# zhab-duino.net
KiCad netlist of a schematic drawn in EAGLE
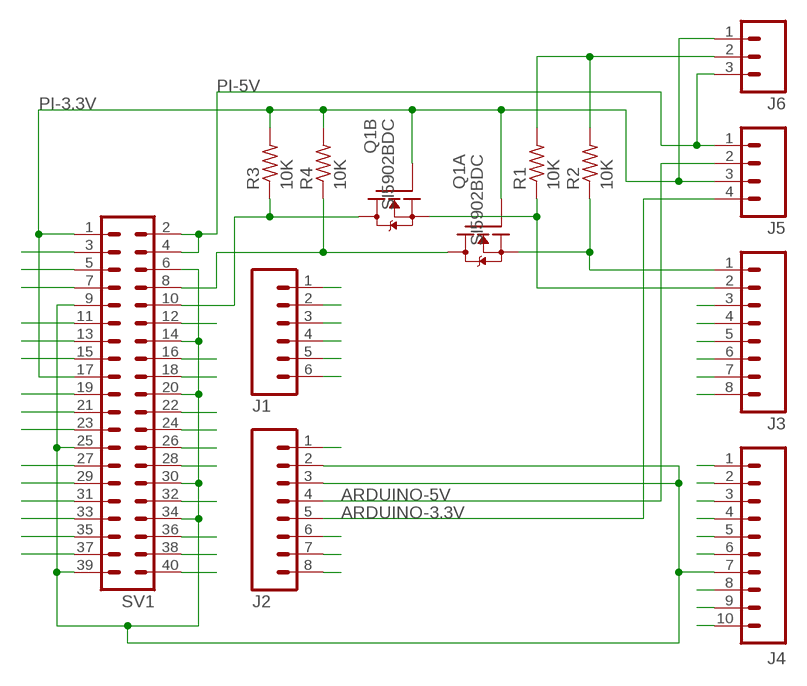
[diagram p0: schematic, sheet 1]

(export (version "E")
  (design (tool "Eeschema 10.0.6"))
  (components
    (comp (ref "J1")
      (value "M06NO_SILK_FEMALE_PTH")
      (footprint "eagle-import:1X06_NO_SILK")
      (libsource (lib "eagle-import") (part "M06NO_SILK_FEMALE_PTH"))
    )
    (comp (ref "J2")
      (value "M08NO_SILK_FEMALE_PTH")
      (footprint "eagle-import:1X08_NO_SILK")
      (libsource (lib "eagle-import") (part "M08NO_SILK_FEMALE_PTH"))
    )
    (comp (ref "J3")
      (value "M08NO_SILK_FEMALE_PTH")
      (footprint "eagle-import:1X08_NO_SILK")
      (libsource (lib "eagle-import") (part "M08NO_SILK_FEMALE_PTH"))
    )
    (comp (ref "J4")
      (value "M10NO_SILK_PTH_FEMALE")
      (footprint "eagle-import:1X10_NO_SILK")
      (libsource (lib "eagle-import") (part "M10NO_SILK_PTH_FEMALE"))
    )
    (comp (ref "J5")
      (value "M04NO_SILK_ALL_ROUND")
      (footprint "eagle-import:1X04_NO_SILK_ALL_ROUND")
      (libsource (lib "eagle-import") (part "M04NO_SILK_ALL_ROUND"))
    )
    (comp (ref "J6")
      (value "M031X03_NO_SILK")
      (footprint "eagle-import:1X03_NO_SILK")
      (libsource (lib "eagle-import") (part "M031X03_NO_SILK"))
    )
    (comp (ref "Q1")
      (value "SI5902BDC")
      (footprint "eagle-import:1206-8CHIP-FET")
      (libsource (lib "eagle-import") (part "SI5902DC"))
    )
    (comp (ref "R1")
      (value "10K")
      (footprint "eagle-import:M1206")
      (libsource (lib "eagle-import") (part "R-US_M1206"))
    )
    (comp (ref "R2")
      (value "10K")
      (footprint "eagle-import:M1206")
      (libsource (lib "eagle-import") (part "R-US_M1206"))
    )
    (comp (ref "R3")
      (value "10K")
      (footprint "eagle-import:M1206")
      (libsource (lib "eagle-import") (part "R-US_M1206"))
    )
    (comp (ref "R4")
      (value "10K")
      (footprint "eagle-import:M1206")
      (libsource (lib "eagle-import") (part "R-US_M1206"))
    )
    (comp (ref "SV1")
      (value "MA20-2")
      (footprint "eagle-import:MA20-2")
      (libsource (lib "eagle-import") (part "MA20-2"))
    )
  )
  (nets
    (net (code "1") (name "/ARDUINO-3.3V") (class "Default")
      (node (ref "J2") (pin "5") (pinfunction "5_5") (pintype "passive"))
      (node (ref "J5") (pin "4") (pinfunction "4_4") (pintype "passive"))
    )
    (net (code "2") (name "/ARDUINO-5V") (class "Default")
      (node (ref "J2") (pin "4") (pinfunction "4_4") (pintype "passive"))
      (node (ref "J5") (pin "2") (pinfunction "2_2") (pintype "passive"))
    )
    (net (code "3") (name "/PI-3.3V") (class "Default")
      (node (ref "J5") (pin "3") (pinfunction "3_3") (pintype "passive"))
      (node (ref "J6") (pin "1") (pinfunction "1_1") (pintype "passive"))
      (node (ref "Q1") (pin "2") (pinfunction "G_2") (pintype "passive"))
      (node (ref "Q1") (pin "4") (pinfunction "G_4") (pintype "passive"))
      (node (ref "R3") (pin "2") (pinfunction "2_2") (pintype "passive"))
      (node (ref "R4") (pin "2") (pinfunction "2_2") (pintype "passive"))
      (node (ref "SV1") (pin "1") (pinfunction "1_1") (pintype "passive"))
      (node (ref "SV1") (pin "17") (pinfunction "17_17") (pintype "passive"))
    )
    (net (code "4") (name "/PI-5V") (class "Default")
      (node (ref "J5") (pin "1") (pinfunction "1_1") (pintype "passive"))
      (node (ref "J6") (pin "3") (pinfunction "3_3") (pintype "passive"))
      (node (ref "SV1") (pin "2") (pinfunction "2_2") (pintype "passive"))
      (node (ref "SV1") (pin "4") (pinfunction "4_4") (pintype "passive"))
    )
    (net (code "5") (name "Net-(J2-Pad2)") (class "Default")
      (node (ref "J2") (pin "2") (pinfunction "2_2") (pintype "passive"))
      (node (ref "J2") (pin "3") (pinfunction "3_3") (pintype "passive"))
      (node (ref "J4") (pin "7") (pinfunction "7_7") (pintype "passive"))
      (node (ref "SV1") (pin "14") (pinfunction "14_14") (pintype "passive"))
      (node (ref "SV1") (pin "20") (pinfunction "20_20") (pintype "passive"))
      (node (ref "SV1") (pin "25") (pinfunction "25_25") (pintype "passive"))
      (node (ref "SV1") (pin "30") (pinfunction "30_30") (pintype "passive"))
      (node (ref "SV1") (pin "34") (pinfunction "34_34") (pintype "passive"))
      (node (ref "SV1") (pin "39") (pinfunction "39_39") (pintype "passive"))
      (node (ref "SV1") (pin "6") (pinfunction "6_6") (pintype "passive"))
      (node (ref "SV1") (pin "9") (pinfunction "9_9") (pintype "passive"))
    )
    (net (code "6") (name "Net-(J6-Pad2)") (class "Default")
      (node (ref "J6") (pin "2") (pinfunction "2_2") (pintype "passive"))
      (node (ref "R1") (pin "2") (pinfunction "2_2") (pintype "passive"))
      (node (ref "R2") (pin "2") (pinfunction "2_2") (pintype "passive"))
    )
    (net (code "7") (name "Net-(Q1A-D-Pad7)") (class "Default")
      (node (ref "Q1") (pin "7") (pinfunction "D_7") (pintype "passive"))
      (node (ref "Q1") (pin "8") (pinfunction "D_8") (pintype "passive"))
      (node (ref "R4") (pin "1") (pinfunction "1_1") (pintype "passive"))
      (node (ref "SV1") (pin "8") (pinfunction "8_8") (pintype "passive"))
    )
    (net (code "8") (name "Net-(Q1A-S)") (class "Default")
      (node (ref "J3") (pin "1") (pinfunction "1_1") (pintype "passive"))
      (node (ref "Q1") (pin "1") (pinfunction "S_1") (pintype "passive"))
      (node (ref "R2") (pin "1") (pinfunction "1_1") (pintype "passive"))
    )
    (net (code "9") (name "Net-(Q1B-D-Pad5)") (class "Default")
      (node (ref "Q1") (pin "5") (pinfunction "D_5") (pintype "passive"))
      (node (ref "Q1") (pin "6") (pinfunction "D_6") (pintype "passive"))
      (node (ref "R3") (pin "1") (pinfunction "1_1") (pintype "passive"))
      (node (ref "SV1") (pin "10") (pinfunction "10_10") (pintype "passive"))
    )
    (net (code "10") (name "Net-(Q1B-S)") (class "Default")
      (node (ref "J3") (pin "2") (pinfunction "2_2") (pintype "passive"))
      (node (ref "Q1") (pin "3") (pinfunction "S_3") (pintype "passive"))
      (node (ref "R1") (pin "1") (pinfunction "1_1") (pintype "passive"))
    )
    (net (code "11") (name "unconnected-(J1-Pad1)") (class "Default")
      (node (ref "J1") (pin "1") (pinfunction "1_1") (pintype "passive"))
    )
    (net (code "12") (name "unconnected-(J1-Pad2)") (class "Default")
      (node (ref "J1") (pin "2") (pinfunction "2_2") (pintype "passive"))
    )
    (net (code "13") (name "unconnected-(J1-Pad3)") (class "Default")
      (node (ref "J1") (pin "3") (pinfunction "3_3") (pintype "passive"))
    )
    (net (code "14") (name "unconnected-(J1-Pad4)") (class "Default")
      (node (ref "J1") (pin "4") (pinfunction "4_4") (pintype "passive"))
    )
    (net (code "15") (name "unconnected-(J1-Pad5)") (class "Default")
      (node (ref "J1") (pin "5") (pinfunction "5_5") (pintype "passive"))
    )
    (net (code "16") (name "unconnected-(J1-Pad6)") (class "Default")
      (node (ref "J1") (pin "6") (pinfunction "6_6") (pintype "passive"))
    )
    (net (code "17") (name "unconnected-(J2-Pad1)") (class "Default")
      (node (ref "J2") (pin "1") (pinfunction "1_1") (pintype "passive"))
    )
    (net (code "18") (name "unconnected-(J2-Pad6)") (class "Default")
      (node (ref "J2") (pin "6") (pinfunction "6_6") (pintype "passive"))
    )
    (net (code "19") (name "unconnected-(J2-Pad7)") (class "Default")
      (node (ref "J2") (pin "7") (pinfunction "7_7") (pintype "passive"))
    )
    (net (code "20") (name "unconnected-(J2-Pad8)") (class "Default")
      (node (ref "J2") (pin "8") (pinfunction "8_8") (pintype "passive"))
    )
    (net (code "21") (name "unconnected-(J3-Pad3)") (class "Default")
      (node (ref "J3") (pin "3") (pinfunction "3_3") (pintype "passive"))
    )
    (net (code "22") (name "unconnected-(J3-Pad4)") (class "Default")
      (node (ref "J3") (pin "4") (pinfunction "4_4") (pintype "passive"))
    )
    (net (code "23") (name "unconnected-(J3-Pad5)") (class "Default")
      (node (ref "J3") (pin "5") (pinfunction "5_5") (pintype "passive"))
    )
    (net (code "24") (name "unconnected-(J3-Pad6)") (class "Default")
      (node (ref "J3") (pin "6") (pinfunction "6_6") (pintype "passive"))
    )
    (net (code "25") (name "unconnected-(J3-Pad7)") (class "Default")
      (node (ref "J3") (pin "7") (pinfunction "7_7") (pintype "passive"))
    )
    (net (code "26") (name "unconnected-(J3-Pad8)") (class "Default")
      (node (ref "J3") (pin "8") (pinfunction "8_8") (pintype "passive"))
    )
    (net (code "27") (name "unconnected-(J4-Pad1)") (class "Default")
      (node (ref "J4") (pin "1") (pinfunction "1_1") (pintype "passive"))
    )
    (net (code "28") (name "unconnected-(J4-Pad2)") (class "Default")
      (node (ref "J4") (pin "2") (pinfunction "2_2") (pintype "passive"))
    )
    (net (code "29") (name "unconnected-(J4-Pad3)") (class "Default")
      (node (ref "J4") (pin "3") (pinfunction "3_3") (pintype "passive"))
    )
    (net (code "30") (name "unconnected-(J4-Pad4)") (class "Default")
      (node (ref "J4") (pin "4") (pinfunction "4_4") (pintype "passive"))
    )
    (net (code "31") (name "unconnected-(J4-Pad5)") (class "Default")
      (node (ref "J4") (pin "5") (pinfunction "5_5") (pintype "passive"))
    )
    (net (code "32") (name "unconnected-(J4-Pad6)") (class "Default")
      (node (ref "J4") (pin "6") (pinfunction "6_6") (pintype "passive"))
    )
    (net (code "33") (name "unconnected-(J4-Pad8)") (class "Default")
      (node (ref "J4") (pin "8") (pinfunction "8_8") (pintype "passive"))
    )
    (net (code "34") (name "unconnected-(J4-Pad9)") (class "Default")
      (node (ref "J4") (pin "9") (pinfunction "9_9") (pintype "passive"))
    )
    (net (code "35") (name "unconnected-(J4-Pad10)") (class "Default")
      (node (ref "J4") (pin "10") (pinfunction "10_10") (pintype "passive"))
    )
    (net (code "36") (name "unconnected-(SV1-Pad3)") (class "Default")
      (node (ref "SV1") (pin "3") (pinfunction "3_3") (pintype "passive"))
    )
    (net (code "37") (name "unconnected-(SV1-Pad5)") (class "Default")
      (node (ref "SV1") (pin "5") (pinfunction "5_5") (pintype "passive"))
    )
    (net (code "38") (name "unconnected-(SV1-Pad7)") (class "Default")
      (node (ref "SV1") (pin "7") (pinfunction "7_7") (pintype "passive"))
    )
    (net (code "39") (name "unconnected-(SV1-Pad11)") (class "Default")
      (node (ref "SV1") (pin "11") (pinfunction "11_11") (pintype "passive"))
    )
    (net (code "40") (name "unconnected-(SV1-Pad12)") (class "Default")
      (node (ref "SV1") (pin "12") (pinfunction "12_12") (pintype "passive"))
    )
    (net (code "41") (name "unconnected-(SV1-Pad13)") (class "Default")
      (node (ref "SV1") (pin "13") (pinfunction "13_13") (pintype "passive"))
    )
    (net (code "42") (name "unconnected-(SV1-Pad15)") (class "Default")
      (node (ref "SV1") (pin "15") (pinfunction "15_15") (pintype "passive"))
    )
    (net (code "43") (name "unconnected-(SV1-Pad16)") (class "Default")
      (node (ref "SV1") (pin "16") (pinfunction "16_16") (pintype "passive"))
    )
    (net (code "44") (name "unconnected-(SV1-Pad18)") (class "Default")
      (node (ref "SV1") (pin "18") (pinfunction "18_18") (pintype "passive"))
    )
    (net (code "45") (name "unconnected-(SV1-Pad19)") (class "Default")
      (node (ref "SV1") (pin "19") (pinfunction "19_19") (pintype "passive"))
    )
    (net (code "46") (name "unconnected-(SV1-Pad21)") (class "Default")
      (node (ref "SV1") (pin "21") (pinfunction "21_21") (pintype "passive"))
    )
    (net (code "47") (name "unconnected-(SV1-Pad22)") (class "Default")
      (node (ref "SV1") (pin "22") (pinfunction "22_22") (pintype "passive"))
    )
    (net (code "48") (name "unconnected-(SV1-Pad23)") (class "Default")
      (node (ref "SV1") (pin "23") (pinfunction "23_23") (pintype "passive"))
    )
    (net (code "49") (name "unconnected-(SV1-Pad24)") (class "Default")
      (node (ref "SV1") (pin "24") (pinfunction "24_24") (pintype "passive"))
    )
    (net (code "50") (name "unconnected-(SV1-Pad26)") (class "Default")
      (node (ref "SV1") (pin "26") (pinfunction "26_26") (pintype "passive"))
    )
    (net (code "51") (name "unconnected-(SV1-Pad27)") (class "Default")
      (node (ref "SV1") (pin "27") (pinfunction "27_27") (pintype "passive"))
    )
    (net (code "52") (name "unconnected-(SV1-Pad28)") (class "Default")
      (node (ref "SV1") (pin "28") (pinfunction "28_28") (pintype "passive"))
    )
    (net (code "53") (name "unconnected-(SV1-Pad29)") (class "Default")
      (node (ref "SV1") (pin "29") (pinfunction "29_29") (pintype "passive"))
    )
    (net (code "54") (name "unconnected-(SV1-Pad31)") (class "Default")
      (node (ref "SV1") (pin "31") (pinfunction "31_31") (pintype "passive"))
    )
    (net (code "55") (name "unconnected-(SV1-Pad32)") (class "Default")
      (node (ref "SV1") (pin "32") (pinfunction "32_32") (pintype "passive"))
    )
    (net (code "56") (name "unconnected-(SV1-Pad33)") (class "Default")
      (node (ref "SV1") (pin "33") (pinfunction "33_33") (pintype "passive"))
    )
    (net (code "57") (name "unconnected-(SV1-Pad35)") (class "Default")
      (node (ref "SV1") (pin "35") (pinfunction "35_35") (pintype "passive"))
    )
    (net (code "58") (name "unconnected-(SV1-Pad36)") (class "Default")
      (node (ref "SV1") (pin "36") (pinfunction "36_36") (pintype "passive"))
    )
    (net (code "59") (name "unconnected-(SV1-Pad37)") (class "Default")
      (node (ref "SV1") (pin "37") (pinfunction "37_37") (pintype "passive"))
    )
    (net (code "60") (name "unconnected-(SV1-Pad38)") (class "Default")
      (node (ref "SV1") (pin "38") (pinfunction "38_38") (pintype "passive"))
    )
    (net (code "61") (name "unconnected-(SV1-Pad40)") (class "Default")
      (node (ref "SV1") (pin "40") (pinfunction "40_40") (pintype "passive"))
    )
  )
)
